# leds.net
KiCad netlist of a schematic drawn in EAGLE
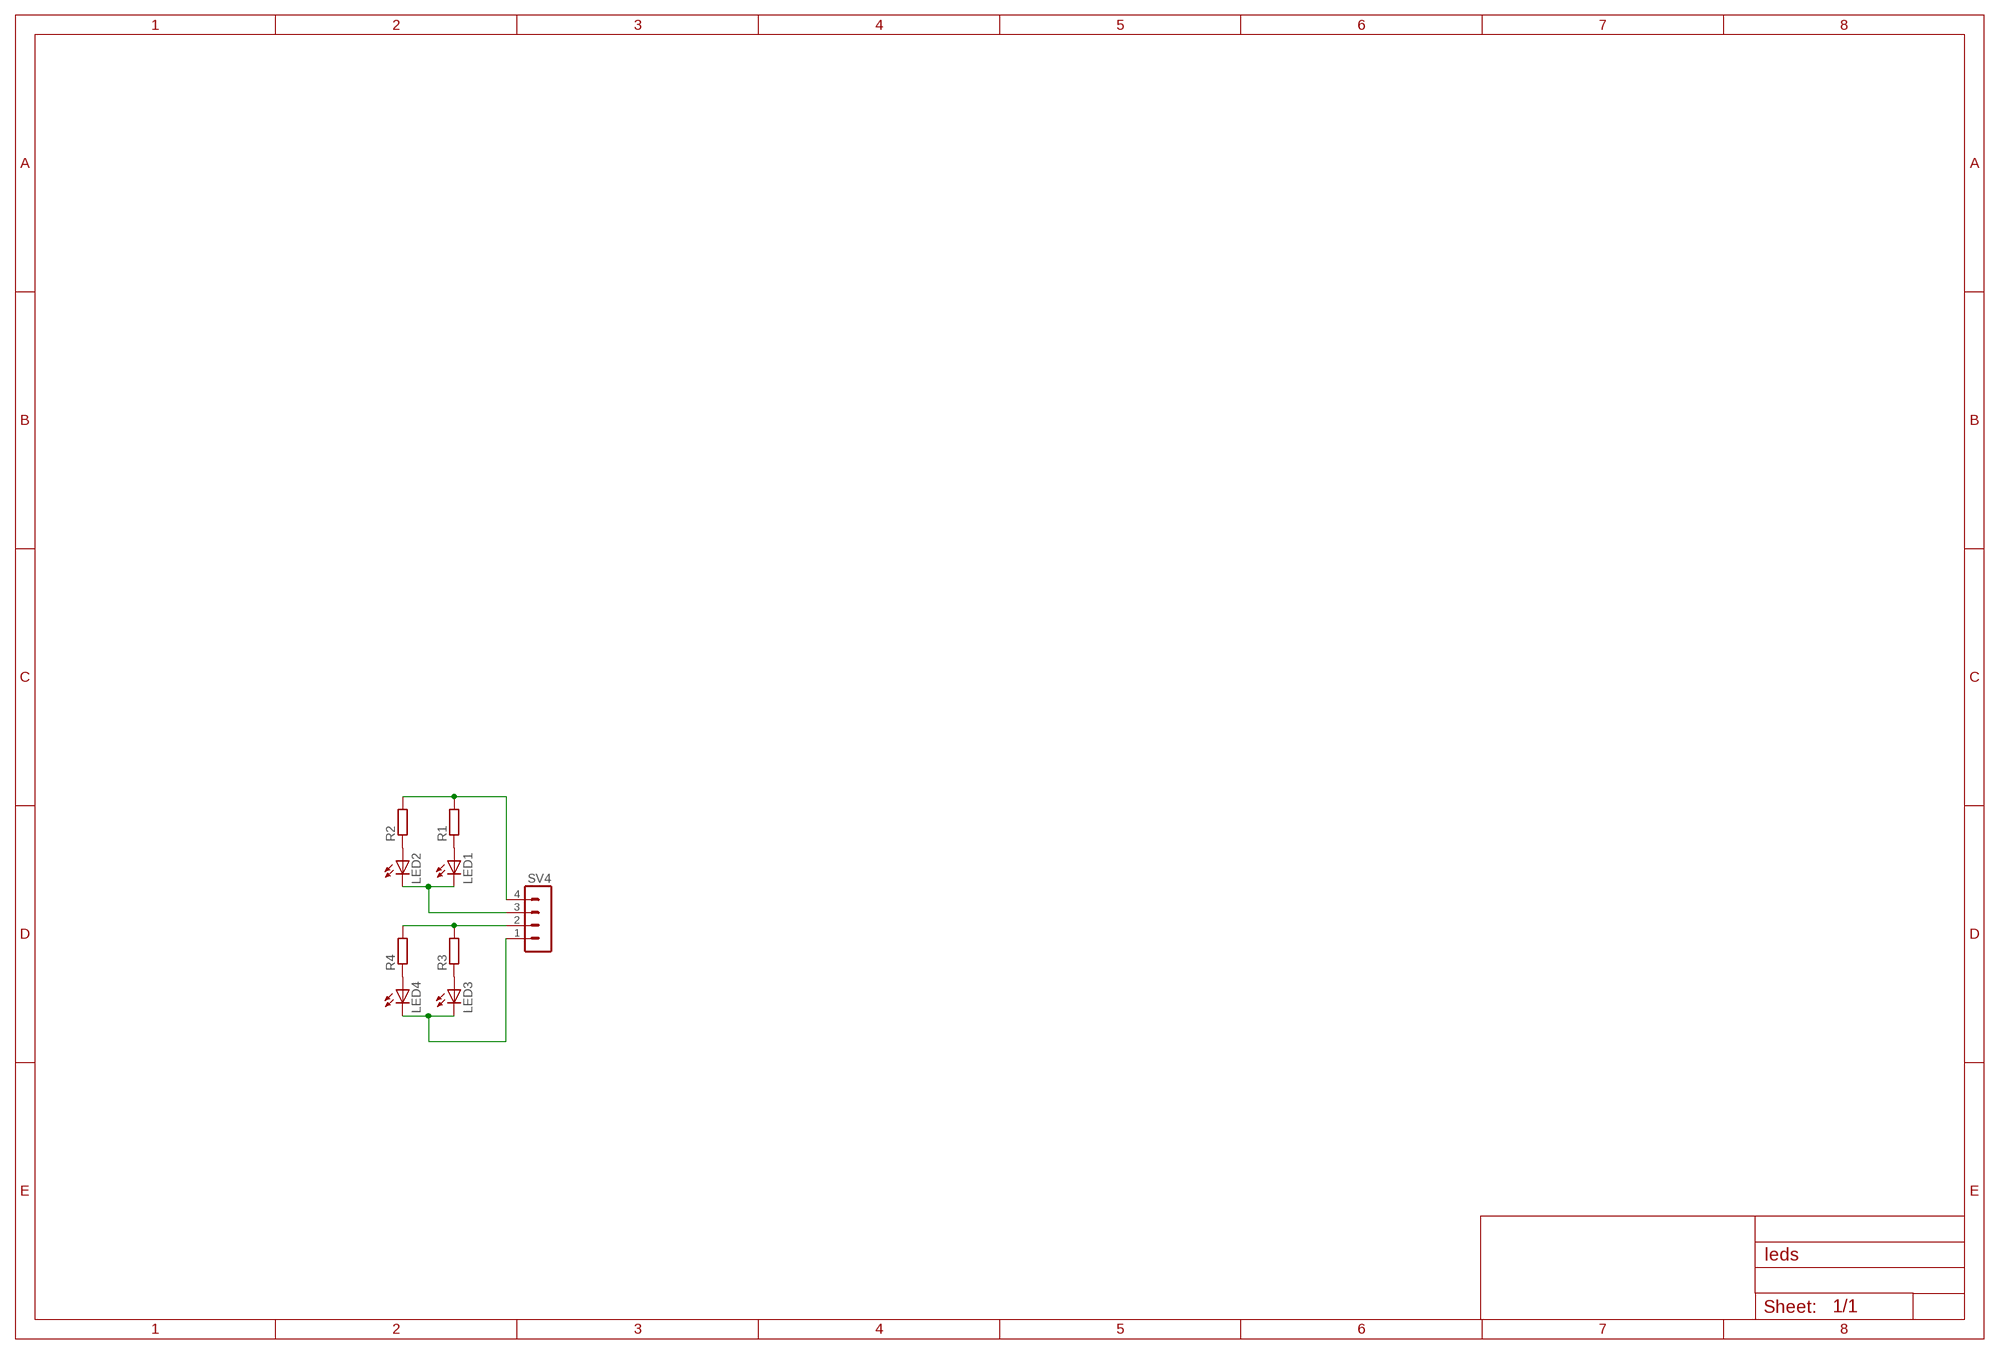
[diagram p0: schematic, sheet 1]

(export (version "E")
  (design (tool "Eeschema 10.0.6"))
  (components
    (comp (ref "LED1")
      (value "LED5MM")
      (footprint "eagle-import:LED5MM")
      (libsource (lib "eagle-import") (part "LED5MM"))
    )
    (comp (ref "LED2")
      (value "LED5MM")
      (footprint "eagle-import:LED5MM")
      (libsource (lib "eagle-import") (part "LED5MM"))
    )
    (comp (ref "LED3")
      (value "LED5MM")
      (footprint "eagle-import:LED5MM")
      (libsource (lib "eagle-import") (part "LED5MM"))
    )
    (comp (ref "LED4")
      (value "LED5MM")
      (footprint "eagle-import:LED5MM")
      (libsource (lib "eagle-import") (part "LED5MM"))
    )
    (comp (ref "R1")
      (value "R-EU_0207/10")
      (footprint "eagle-import:0207_10")
      (libsource (lib "eagle-import") (part "R-EU_0207/10"))
    )
    (comp (ref "R2")
      (value "R-EU_0207/10")
      (footprint "eagle-import:0207_10")
      (libsource (lib "eagle-import") (part "R-EU_0207/10"))
    )
    (comp (ref "R3")
      (value "R-EU_0207/10")
      (footprint "eagle-import:0207_10")
      (libsource (lib "eagle-import") (part "R-EU_0207/10"))
    )
    (comp (ref "R4")
      (value "R-EU_0207/10")
      (footprint "eagle-import:0207_10")
      (libsource (lib "eagle-import") (part "R-EU_0207/10"))
    )
    (comp (ref "SV4")
      (value "MA04-1")
      (footprint "eagle-import:MA04-1")
      (libsource (lib "eagle-import") (part "MA04-1"))
    )
  )
  (nets
    (net (code "1") (name "Net-(LED1-C)") (class "Default")
      (node (ref "LED1") (pin "K") (pinfunction "C_K") (pintype "passive"))
      (node (ref "LED2") (pin "K") (pinfunction "C_K") (pintype "passive"))
      (node (ref "SV4") (pin "3") (pinfunction "3_3") (pintype "passive"))
    )
    (net (code "2") (name "Net-(LED1-PadA)") (class "Default")
      (node (ref "LED1") (pin "A") (pinfunction "A_A") (pintype "passive"))
      (node (ref "R1") (pin "1") (pinfunction "1_1") (pintype "passive"))
    )
    (net (code "3") (name "Net-(LED2-PadA)") (class "Default")
      (node (ref "LED2") (pin "A") (pinfunction "A_A") (pintype "passive"))
      (node (ref "R2") (pin "1") (pinfunction "1_1") (pintype "passive"))
    )
    (net (code "4") (name "Net-(LED3-C)") (class "Default")
      (node (ref "LED3") (pin "K") (pinfunction "C_K") (pintype "passive"))
      (node (ref "LED4") (pin "K") (pinfunction "C_K") (pintype "passive"))
      (node (ref "SV4") (pin "1") (pinfunction "1_1") (pintype "passive"))
    )
    (net (code "5") (name "Net-(LED3-PadA)") (class "Default")
      (node (ref "LED3") (pin "A") (pinfunction "A_A") (pintype "passive"))
      (node (ref "R3") (pin "1") (pinfunction "1_1") (pintype "passive"))
    )
    (net (code "6") (name "Net-(LED4-PadA)") (class "Default")
      (node (ref "LED4") (pin "A") (pinfunction "A_A") (pintype "passive"))
      (node (ref "R4") (pin "1") (pinfunction "1_1") (pintype "passive"))
    )
    (net (code "7") (name "Net-(R1-Pad2)") (class "Default")
      (node (ref "R1") (pin "2") (pinfunction "2_2") (pintype "passive"))
      (node (ref "R2") (pin "2") (pinfunction "2_2") (pintype "passive"))
      (node (ref "SV4") (pin "4") (pinfunction "4_4") (pintype "passive"))
    )
    (net (code "8") (name "Net-(R3-Pad2)") (class "Default")
      (node (ref "R3") (pin "2") (pinfunction "2_2") (pintype "passive"))
      (node (ref "R4") (pin "2") (pinfunction "2_2") (pintype "passive"))
      (node (ref "SV4") (pin "2") (pinfunction "2_2") (pintype "passive"))
    )
  )
)
